# Sheet1.net
KiCad netlist of a schematic drawn in Altium Designer
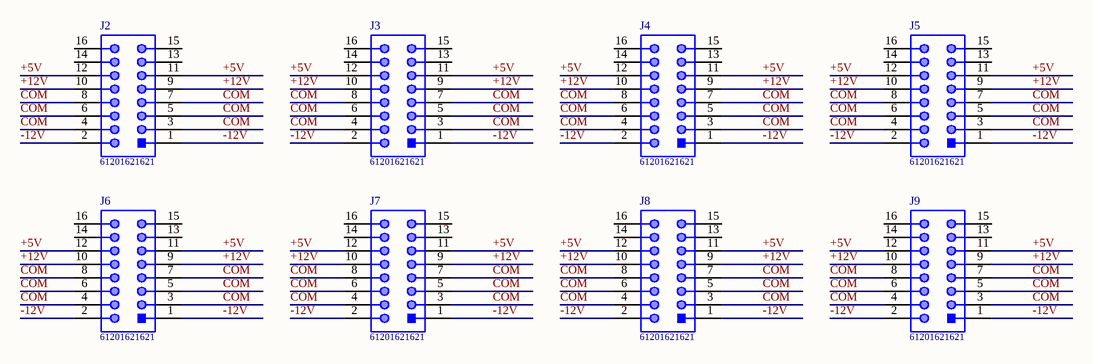
[diagram p0: Sheet1.SchDoc]

(export (version "E")
  (design (tool "Eeschema 10.0.6"))
  (components
    (comp (ref "J2")
      (value "61201621621")
      (footprint "61201621621")
      (description "Male Box Header WR-BHD, THT, Vertical, pitch 2.54 mm, 16 pins")
      (fields (field (name "MANUFACTURER") "Wurth Elektronik") (field (name "PUBLISHER") "WurthElektronik"))
      (libsource (lib "Altium Content Vault") (part "WE-CN-2P-M-R16"))
    )
    (comp (ref "J3")
      (value "61201621621")
      (footprint "61201621621")
      (description "Male Box Header WR-BHD, THT, Vertical, pitch 2.54 mm, 16 pins")
      (fields (field (name "MANUFACTURER") "Wurth Elektronik") (field (name "PUBLISHER") "WurthElektronik"))
      (libsource (lib "Altium Content Vault") (part "WE-CN-2P-M-R16"))
    )
    (comp (ref "J4")
      (value "61201621621")
      (footprint "61201621621")
      (description "Male Box Header WR-BHD, THT, Vertical, pitch 2.54 mm, 16 pins")
      (fields (field (name "MANUFACTURER") "Wurth Elektronik") (field (name "PUBLISHER") "WurthElektronik"))
      (libsource (lib "Altium Content Vault") (part "WE-CN-2P-M-R16"))
    )
    (comp (ref "J5")
      (value "61201621621")
      (footprint "61201621621")
      (description "Male Box Header WR-BHD, THT, Vertical, pitch 2.54 mm, 16 pins")
      (fields (field (name "MANUFACTURER") "Wurth Elektronik") (field (name "PUBLISHER") "WurthElektronik"))
      (libsource (lib "Altium Content Vault") (part "WE-CN-2P-M-R16"))
    )
    (comp (ref "J6")
      (value "61201621621")
      (footprint "61201621621")
      (description "Male Box Header WR-BHD, THT, Vertical, pitch 2.54 mm, 16 pins")
      (fields (field (name "MANUFACTURER") "Wurth Elektronik") (field (name "PUBLISHER") "WurthElektronik"))
      (libsource (lib "Altium Content Vault") (part "WE-CN-2P-M-R16"))
    )
    (comp (ref "J7")
      (value "61201621621")
      (footprint "61201621621")
      (description "Male Box Header WR-BHD, THT, Vertical, pitch 2.54 mm, 16 pins")
      (fields (field (name "MANUFACTURER") "Wurth Elektronik") (field (name "PUBLISHER") "WurthElektronik"))
      (libsource (lib "Altium Content Vault") (part "WE-CN-2P-M-R16"))
    )
    (comp (ref "J8")
      (value "61201621621")
      (footprint "61201621621")
      (description "Male Box Header WR-BHD, THT, Vertical, pitch 2.54 mm, 16 pins")
      (fields (field (name "MANUFACTURER") "Wurth Elektronik") (field (name "PUBLISHER") "WurthElektronik"))
      (libsource (lib "Altium Content Vault") (part "WE-CN-2P-M-R16"))
    )
    (comp (ref "J9")
      (value "61201621621")
      (footprint "61201621621")
      (description "Male Box Header WR-BHD, THT, Vertical, pitch 2.54 mm, 16 pins")
      (fields (field (name "MANUFACTURER") "Wurth Elektronik") (field (name "PUBLISHER") "WurthElektronik"))
      (libsource (lib "Altium Content Vault") (part "WE-CN-2P-M-R16"))
    )
  )
  (nets
    (net (code "1") (name "/+5V") (class "Default")
      (node (ref "J2") (pin "11") (pinfunction "11_11") (pintype "passive"))
      (node (ref "J2") (pin "12") (pinfunction "12_12") (pintype "passive"))
      (node (ref "J3") (pin "11") (pinfunction "11_11") (pintype "passive"))
      (node (ref "J3") (pin "12") (pinfunction "12_12") (pintype "passive"))
      (node (ref "J4") (pin "11") (pinfunction "11_11") (pintype "passive"))
      (node (ref "J4") (pin "12") (pinfunction "12_12") (pintype "passive"))
      (node (ref "J5") (pin "11") (pinfunction "11_11") (pintype "passive"))
      (node (ref "J5") (pin "12") (pinfunction "12_12") (pintype "passive"))
      (node (ref "J6") (pin "11") (pinfunction "11_11") (pintype "passive"))
      (node (ref "J6") (pin "12") (pinfunction "12_12") (pintype "passive"))
      (node (ref "J7") (pin "11") (pinfunction "11_11") (pintype "passive"))
      (node (ref "J7") (pin "12") (pinfunction "12_12") (pintype "passive"))
      (node (ref "J8") (pin "11") (pinfunction "11_11") (pintype "passive"))
      (node (ref "J8") (pin "12") (pinfunction "12_12") (pintype "passive"))
      (node (ref "J9") (pin "11") (pinfunction "11_11") (pintype "passive"))
      (node (ref "J9") (pin "12") (pinfunction "12_12") (pintype "passive"))
    )
    (net (code "2") (name "/+12V") (class "Default")
      (node (ref "J2") (pin "10") (pinfunction "10_10") (pintype "passive"))
      (node (ref "J2") (pin "9") (pinfunction "9_9") (pintype "passive"))
      (node (ref "J3") (pin "10") (pinfunction "10_10") (pintype "passive"))
      (node (ref "J3") (pin "9") (pinfunction "9_9") (pintype "passive"))
      (node (ref "J4") (pin "10") (pinfunction "10_10") (pintype "passive"))
      (node (ref "J4") (pin "9") (pinfunction "9_9") (pintype "passive"))
      (node (ref "J5") (pin "10") (pinfunction "10_10") (pintype "passive"))
      (node (ref "J5") (pin "9") (pinfunction "9_9") (pintype "passive"))
      (node (ref "J6") (pin "10") (pinfunction "10_10") (pintype "passive"))
      (node (ref "J6") (pin "9") (pinfunction "9_9") (pintype "passive"))
      (node (ref "J7") (pin "10") (pinfunction "10_10") (pintype "passive"))
      (node (ref "J7") (pin "9") (pinfunction "9_9") (pintype "passive"))
      (node (ref "J8") (pin "10") (pinfunction "10_10") (pintype "passive"))
      (node (ref "J8") (pin "9") (pinfunction "9_9") (pintype "passive"))
      (node (ref "J9") (pin "10") (pinfunction "10_10") (pintype "passive"))
      (node (ref "J9") (pin "9") (pinfunction "9_9") (pintype "passive"))
    )
    (net (code "3") (name "/-12V") (class "Default")
      (node (ref "J2") (pin "1") (pinfunction "1_1") (pintype "passive"))
      (node (ref "J2") (pin "2") (pinfunction "2_2") (pintype "passive"))
      (node (ref "J3") (pin "1") (pinfunction "1_1") (pintype "passive"))
      (node (ref "J3") (pin "2") (pinfunction "2_2") (pintype "passive"))
      (node (ref "J4") (pin "1") (pinfunction "1_1") (pintype "passive"))
      (node (ref "J4") (pin "2") (pinfunction "2_2") (pintype "passive"))
      (node (ref "J5") (pin "1") (pinfunction "1_1") (pintype "passive"))
      (node (ref "J5") (pin "2") (pinfunction "2_2") (pintype "passive"))
      (node (ref "J6") (pin "1") (pinfunction "1_1") (pintype "passive"))
      (node (ref "J6") (pin "2") (pinfunction "2_2") (pintype "passive"))
      (node (ref "J7") (pin "1") (pinfunction "1_1") (pintype "passive"))
      (node (ref "J7") (pin "2") (pinfunction "2_2") (pintype "passive"))
      (node (ref "J8") (pin "1") (pinfunction "1_1") (pintype "passive"))
      (node (ref "J8") (pin "2") (pinfunction "2_2") (pintype "passive"))
      (node (ref "J9") (pin "1") (pinfunction "1_1") (pintype "passive"))
      (node (ref "J9") (pin "2") (pinfunction "2_2") (pintype "passive"))
    )
    (net (code "4") (name "/COM") (class "Default")
      (node (ref "J2") (pin "3") (pinfunction "3_3") (pintype "passive"))
      (node (ref "J2") (pin "4") (pinfunction "4_4") (pintype "passive"))
      (node (ref "J2") (pin "5") (pinfunction "5_5") (pintype "passive"))
      (node (ref "J2") (pin "6") (pinfunction "6_6") (pintype "passive"))
      (node (ref "J2") (pin "7") (pinfunction "7_7") (pintype "passive"))
      (node (ref "J2") (pin "8") (pinfunction "8_8") (pintype "passive"))
      (node (ref "J3") (pin "3") (pinfunction "3_3") (pintype "passive"))
      (node (ref "J3") (pin "4") (pinfunction "4_4") (pintype "passive"))
      (node (ref "J3") (pin "5") (pinfunction "5_5") (pintype "passive"))
      (node (ref "J3") (pin "6") (pinfunction "6_6") (pintype "passive"))
      (node (ref "J3") (pin "7") (pinfunction "7_7") (pintype "passive"))
      (node (ref "J3") (pin "8") (pinfunction "8_8") (pintype "passive"))
      (node (ref "J4") (pin "3") (pinfunction "3_3") (pintype "passive"))
      (node (ref "J4") (pin "4") (pinfunction "4_4") (pintype "passive"))
      (node (ref "J4") (pin "5") (pinfunction "5_5") (pintype "passive"))
      (node (ref "J4") (pin "6") (pinfunction "6_6") (pintype "passive"))
      (node (ref "J4") (pin "7") (pinfunction "7_7") (pintype "passive"))
      (node (ref "J4") (pin "8") (pinfunction "8_8") (pintype "passive"))
      (node (ref "J5") (pin "3") (pinfunction "3_3") (pintype "passive"))
      (node (ref "J5") (pin "4") (pinfunction "4_4") (pintype "passive"))
      (node (ref "J5") (pin "5") (pinfunction "5_5") (pintype "passive"))
      (node (ref "J5") (pin "6") (pinfunction "6_6") (pintype "passive"))
      (node (ref "J5") (pin "7") (pinfunction "7_7") (pintype "passive"))
      (node (ref "J5") (pin "8") (pinfunction "8_8") (pintype "passive"))
      (node (ref "J6") (pin "3") (pinfunction "3_3") (pintype "passive"))
      (node (ref "J6") (pin "4") (pinfunction "4_4") (pintype "passive"))
      (node (ref "J6") (pin "5") (pinfunction "5_5") (pintype "passive"))
      (node (ref "J6") (pin "6") (pinfunction "6_6") (pintype "passive"))
      (node (ref "J6") (pin "7") (pinfunction "7_7") (pintype "passive"))
      (node (ref "J6") (pin "8") (pinfunction "8_8") (pintype "passive"))
      (node (ref "J7") (pin "3") (pinfunction "3_3") (pintype "passive"))
      (node (ref "J7") (pin "4") (pinfunction "4_4") (pintype "passive"))
      (node (ref "J7") (pin "5") (pinfunction "5_5") (pintype "passive"))
      (node (ref "J7") (pin "6") (pinfunction "6_6") (pintype "passive"))
      (node (ref "J7") (pin "7") (pinfunction "7_7") (pintype "passive"))
      (node (ref "J7") (pin "8") (pinfunction "8_8") (pintype "passive"))
      (node (ref "J8") (pin "3") (pinfunction "3_3") (pintype "passive"))
      (node (ref "J8") (pin "4") (pinfunction "4_4") (pintype "passive"))
      (node (ref "J8") (pin "5") (pinfunction "5_5") (pintype "passive"))
      (node (ref "J8") (pin "6") (pinfunction "6_6") (pintype "passive"))
      (node (ref "J8") (pin "7") (pinfunction "7_7") (pintype "passive"))
      (node (ref "J8") (pin "8") (pinfunction "8_8") (pintype "passive"))
      (node (ref "J9") (pin "3") (pinfunction "3_3") (pintype "passive"))
      (node (ref "J9") (pin "4") (pinfunction "4_4") (pintype "passive"))
      (node (ref "J9") (pin "5") (pinfunction "5_5") (pintype "passive"))
      (node (ref "J9") (pin "6") (pinfunction "6_6") (pintype "passive"))
      (node (ref "J9") (pin "7") (pinfunction "7_7") (pintype "passive"))
      (node (ref "J9") (pin "8") (pinfunction "8_8") (pintype "passive"))
    )
    (net (code "5") (name "unconnected-(J2-Pad13)") (class "Default")
      (node (ref "J2") (pin "13") (pinfunction "13_13") (pintype "passive"))
    )
    (net (code "6") (name "unconnected-(J2-Pad14)") (class "Default")
      (node (ref "J2") (pin "14") (pinfunction "14_14") (pintype "passive"))
    )
    (net (code "7") (name "unconnected-(J2-Pad15)") (class "Default")
      (node (ref "J2") (pin "15") (pinfunction "15_15") (pintype "passive"))
    )
    (net (code "8") (name "unconnected-(J2-Pad16)") (class "Default")
      (node (ref "J2") (pin "16") (pinfunction "16_16") (pintype "passive"))
    )
    (net (code "9") (name "unconnected-(J3-Pad13)") (class "Default")
      (node (ref "J3") (pin "13") (pinfunction "13_13") (pintype "passive"))
    )
    (net (code "10") (name "unconnected-(J3-Pad14)") (class "Default")
      (node (ref "J3") (pin "14") (pinfunction "14_14") (pintype "passive"))
    )
    (net (code "11") (name "unconnected-(J3-Pad15)") (class "Default")
      (node (ref "J3") (pin "15") (pinfunction "15_15") (pintype "passive"))
    )
    (net (code "12") (name "unconnected-(J3-Pad16)") (class "Default")
      (node (ref "J3") (pin "16") (pinfunction "16_16") (pintype "passive"))
    )
    (net (code "13") (name "unconnected-(J4-Pad13)") (class "Default")
      (node (ref "J4") (pin "13") (pinfunction "13_13") (pintype "passive"))
    )
    (net (code "14") (name "unconnected-(J4-Pad14)") (class "Default")
      (node (ref "J4") (pin "14") (pinfunction "14_14") (pintype "passive"))
    )
    (net (code "15") (name "unconnected-(J4-Pad15)") (class "Default")
      (node (ref "J4") (pin "15") (pinfunction "15_15") (pintype "passive"))
    )
    (net (code "16") (name "unconnected-(J4-Pad16)") (class "Default")
      (node (ref "J4") (pin "16") (pinfunction "16_16") (pintype "passive"))
    )
    (net (code "17") (name "unconnected-(J5-Pad13)") (class "Default")
      (node (ref "J5") (pin "13") (pinfunction "13_13") (pintype "passive"))
    )
    (net (code "18") (name "unconnected-(J5-Pad14)") (class "Default")
      (node (ref "J5") (pin "14") (pinfunction "14_14") (pintype "passive"))
    )
    (net (code "19") (name "unconnected-(J5-Pad15)") (class "Default")
      (node (ref "J5") (pin "15") (pinfunction "15_15") (pintype "passive"))
    )
    (net (code "20") (name "unconnected-(J5-Pad16)") (class "Default")
      (node (ref "J5") (pin "16") (pinfunction "16_16") (pintype "passive"))
    )
    (net (code "21") (name "unconnected-(J6-Pad13)") (class "Default")
      (node (ref "J6") (pin "13") (pinfunction "13_13") (pintype "passive"))
    )
    (net (code "22") (name "unconnected-(J6-Pad14)") (class "Default")
      (node (ref "J6") (pin "14") (pinfunction "14_14") (pintype "passive"))
    )
    (net (code "23") (name "unconnected-(J6-Pad15)") (class "Default")
      (node (ref "J6") (pin "15") (pinfunction "15_15") (pintype "passive"))
    )
    (net (code "24") (name "unconnected-(J6-Pad16)") (class "Default")
      (node (ref "J6") (pin "16") (pinfunction "16_16") (pintype "passive"))
    )
    (net (code "25") (name "unconnected-(J7-Pad13)") (class "Default")
      (node (ref "J7") (pin "13") (pinfunction "13_13") (pintype "passive"))
    )
    (net (code "26") (name "unconnected-(J7-Pad14)") (class "Default")
      (node (ref "J7") (pin "14") (pinfunction "14_14") (pintype "passive"))
    )
    (net (code "27") (name "unconnected-(J7-Pad15)") (class "Default")
      (node (ref "J7") (pin "15") (pinfunction "15_15") (pintype "passive"))
    )
    (net (code "28") (name "unconnected-(J7-Pad16)") (class "Default")
      (node (ref "J7") (pin "16") (pinfunction "16_16") (pintype "passive"))
    )
    (net (code "29") (name "unconnected-(J8-Pad13)") (class "Default")
      (node (ref "J8") (pin "13") (pinfunction "13_13") (pintype "passive"))
    )
    (net (code "30") (name "unconnected-(J8-Pad14)") (class "Default")
      (node (ref "J8") (pin "14") (pinfunction "14_14") (pintype "passive"))
    )
    (net (code "31") (name "unconnected-(J8-Pad15)") (class "Default")
      (node (ref "J8") (pin "15") (pinfunction "15_15") (pintype "passive"))
    )
    (net (code "32") (name "unconnected-(J8-Pad16)") (class "Default")
      (node (ref "J8") (pin "16") (pinfunction "16_16") (pintype "passive"))
    )
    (net (code "33") (name "unconnected-(J9-Pad13)") (class "Default")
      (node (ref "J9") (pin "13") (pinfunction "13_13") (pintype "passive"))
    )
    (net (code "34") (name "unconnected-(J9-Pad14)") (class "Default")
      (node (ref "J9") (pin "14") (pinfunction "14_14") (pintype "passive"))
    )
    (net (code "35") (name "unconnected-(J9-Pad15)") (class "Default")
      (node (ref "J9") (pin "15") (pinfunction "15_15") (pintype "passive"))
    )
    (net (code "36") (name "unconnected-(J9-Pad16)") (class "Default")
      (node (ref "J9") (pin "16") (pinfunction "16_16") (pintype "passive"))
    )
  )
)
